# AVR_S1.net
KiCad netlist of a schematic drawn in EAGLE
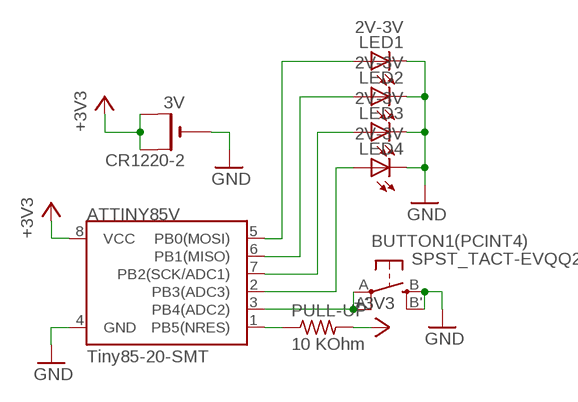
[diagram p0: schematic, sheet 1]

(export (version "E")
  (design (tool "Eeschema 10.0.6"))
  (components
    (comp (ref "ATTINY85V")
      (value "Tiny85-20-SMT")
      (footprint "eagle-import:SO08-EIAJ")
      (libsource (lib "eagle-import") (part "ATTINY45TINY85-20-SMT"))
    )
    (comp (ref "BUTTON1(PCINT4)")
      (value "SPST_TACT-EVQQ2")
      (footprint "eagle-import:EVQ-Q2")
      (libsource (lib "eagle-import") (part "SPST_TACT-EVQQ2"))
    )
    (comp (ref "CR1220-2")
      (value "3V")
      (footprint "eagle-import:CR1220-SMD")
      (libsource (lib "eagle-import") (part "CR1220SMT"))
    )
    (comp (ref "LED1")
      (value "2V-3V")
      (footprint "eagle-import:SML0805")
      (libsource (lib "eagle-import") (part "LEDSML0805"))
    )
    (comp (ref "LED2")
      (value "2V-3V")
      (footprint "eagle-import:SML0805")
      (libsource (lib "eagle-import") (part "LEDSML0805"))
    )
    (comp (ref "LED3")
      (value "2V-3V")
      (footprint "eagle-import:SML0805")
      (libsource (lib "eagle-import") (part "LEDSML0805"))
    )
    (comp (ref "LED4")
      (value "2V-3V")
      (footprint "eagle-import:SML0805")
      (libsource (lib "eagle-import") (part "LEDSML0805"))
    )
    (comp (ref "PULL-UP")
      (value "10 KOhm")
      (footprint "eagle-import:M0805")
      (libsource (lib "eagle-import") (part "R-US_M0805"))
    )
  )
  (nets
    (net (code "1") (name "+3V3") (class "Default")
      (node (ref "ATTINY85V") (pin "8") (pinfunction "VCC_8") (pintype "bidirectional"))
      (node (ref "CR1220-2") (pin "+$1") (pinfunction "+_+$1") (pintype "passive"))
      (node (ref "CR1220-2") (pin "+$2") (pinfunction "+1_+$2") (pintype "passive"))
      (node (ref "PULL-UP") (pin "2") (pinfunction "2_2") (pintype "passive"))
    )
    (net (code "2") (name "GND") (class "Default")
      (node (ref "ATTINY85V") (pin "4") (pinfunction "GND_4") (pintype "bidirectional"))
      (node (ref "BUTTON1(PCINT4)") (pin "B") (pinfunction "S_B") (pintype "passive"))
      (node (ref "BUTTON1(PCINT4)") (pin "B'") (pinfunction "S1_B'") (pintype "passive"))
      (node (ref "CR1220-2") (pin "-") (pinfunction "-_-") (pintype "passive"))
      (node (ref "LED1") (pin "C") (pinfunction "C_C") (pintype "passive"))
      (node (ref "LED2") (pin "C") (pinfunction "C_C") (pintype "passive"))
      (node (ref "LED3") (pin "C") (pinfunction "C_C") (pintype "passive"))
      (node (ref "LED4") (pin "C") (pinfunction "C_C") (pintype "passive"))
    )
    (net (code "3") (name "Net-(ATTINY85V-PB0(MOSI))") (class "Default")
      (node (ref "ATTINY85V") (pin "5") (pinfunction "PB0(MOSI)_5") (pintype "bidirectional"))
      (node (ref "LED1") (pin "A") (pinfunction "A_A") (pintype "passive"))
    )
    (net (code "4") (name "Net-(ATTINY85V-PB1(MISO))") (class "Default")
      (node (ref "ATTINY85V") (pin "6") (pinfunction "PB1(MISO)_6") (pintype "bidirectional"))
      (node (ref "LED2") (pin "A") (pinfunction "A_A") (pintype "passive"))
    )
    (net (code "5") (name "Net-(ATTINY85V-PB2(SCK{slash}ADC1))") (class "Default")
      (node (ref "ATTINY85V") (pin "7") (pinfunction "PB2(SCK/ADC1)_7") (pintype "bidirectional"))
      (node (ref "LED3") (pin "A") (pinfunction "A_A") (pintype "passive"))
    )
    (net (code "6") (name "Net-(ATTINY85V-PB3(ADC3))") (class "Default")
      (node (ref "ATTINY85V") (pin "2") (pinfunction "PB3(ADC3)_2") (pintype "bidirectional"))
      (node (ref "LED4") (pin "A") (pinfunction "A_A") (pintype "passive"))
    )
    (net (code "7") (name "Net-(ATTINY85V-PB4(ADC2))") (class "Default")
      (node (ref "ATTINY85V") (pin "3") (pinfunction "PB4(ADC2)_3") (pintype "bidirectional"))
      (node (ref "BUTTON1(PCINT4)") (pin "A") (pinfunction "P_A") (pintype "passive"))
      (node (ref "BUTTON1(PCINT4)") (pin "A'") (pinfunction "P1_A'") (pintype "passive"))
    )
    (net (code "8") (name "Net-(ATTINY85V-PB5(NRES))") (class "Default")
      (node (ref "ATTINY85V") (pin "1") (pinfunction "PB5(NRES)_1") (pintype "bidirectional"))
      (node (ref "PULL-UP") (pin "1") (pinfunction "1_1") (pintype "passive"))
    )
  )
)
